# Mosfet_Board.net
KiCad netlist of a schematic drawn in Altium Designer
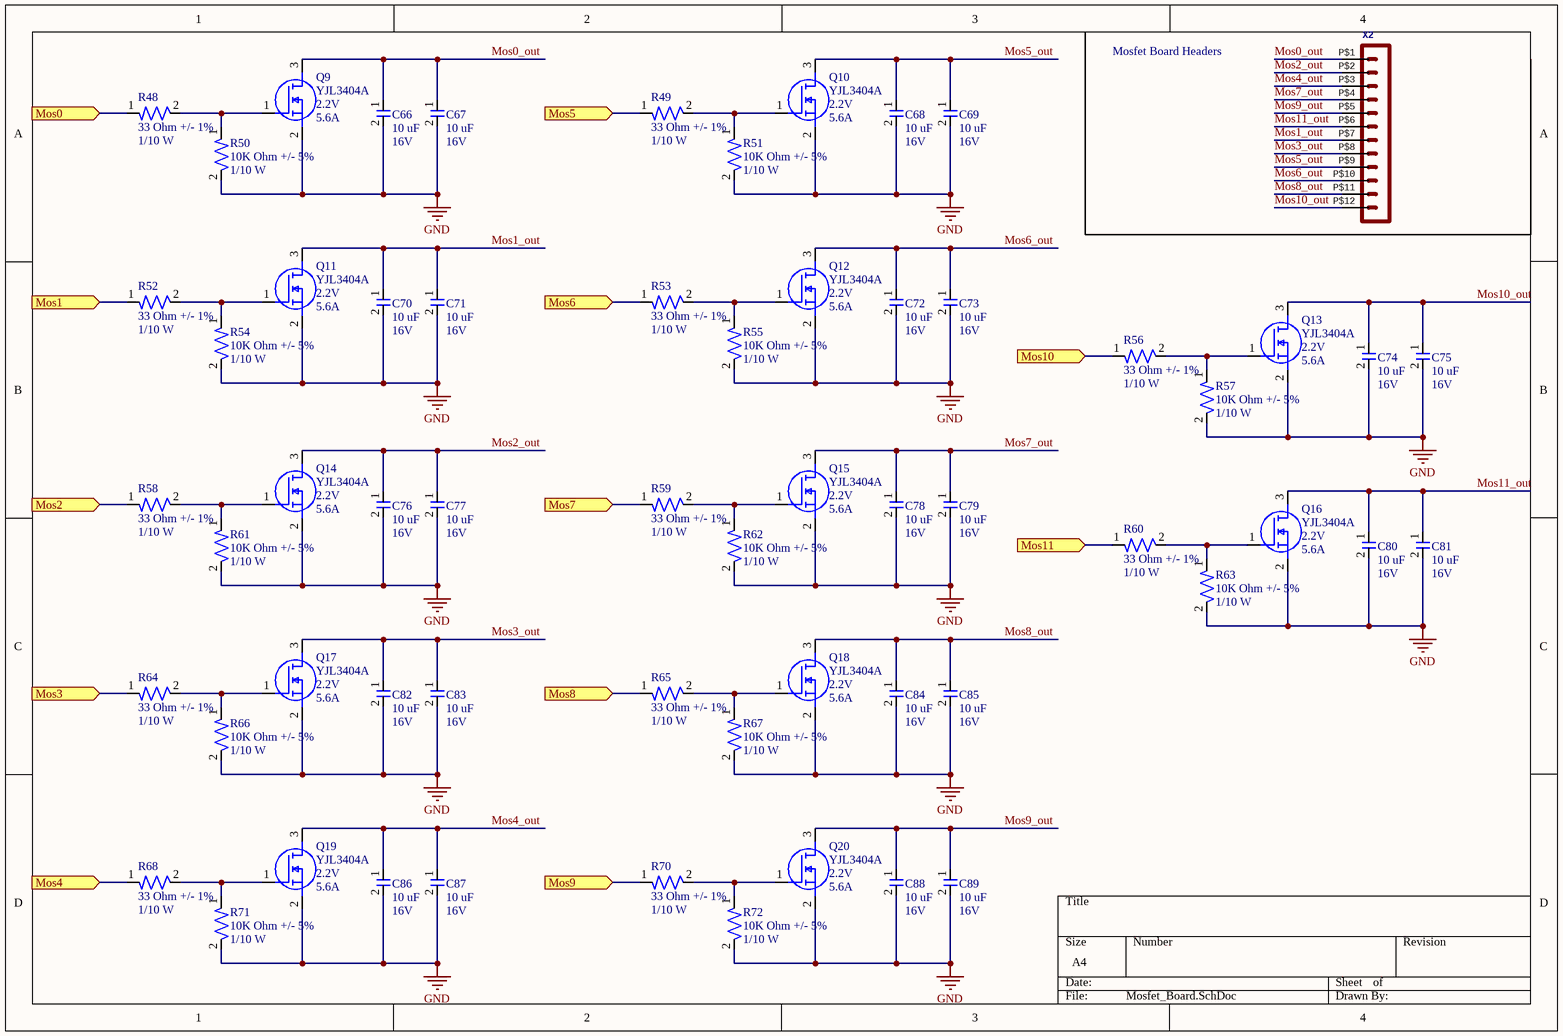
[diagram p0: Mosfet_Board.SchDoc]

(export (version "E")
  (design (tool "Eeschema 10.0.6"))
  (components
    (comp (ref "C66")
      (value "MCS1802GS-20-Z")
      (footprint "CAP-0805")
      (description "10 µF ±10% 16V Ceramic Capacitor X7R 0805 (2012 Metric)")
      (fields (field (name "CAPACITANCE") "10 uF") (field (name "VOLTAGE RATING") "16V"))
      (libsource (lib "MasterLib") (part "CAP-10U-0002"))
    )
    (comp (ref "C67")
      (value "MCS1802GS-20-Z")
      (footprint "CAP-0805")
      (description "10 µF ±10% 16V Ceramic Capacitor X7R 0805 (2012 Metric)")
      (fields (field (name "CAPACITANCE") "10 uF") (field (name "VOLTAGE RATING") "16V"))
      (libsource (lib "MasterLib") (part "CAP-10U-0002"))
    )
    (comp (ref "C68")
      (value "MCS1802GS-20-Z")
      (footprint "CAP-0805")
      (description "10 µF ±10% 16V Ceramic Capacitor X7R 0805 (2012 Metric)")
      (fields (field (name "CAPACITANCE") "10 uF") (field (name "VOLTAGE RATING") "16V"))
      (libsource (lib "MasterLib") (part "CAP-10U-0002"))
    )
    (comp (ref "C69")
      (value "MCS1802GS-20-Z")
      (footprint "CAP-0805")
      (description "10 µF ±10% 16V Ceramic Capacitor X7R 0805 (2012 Metric)")
      (fields (field (name "CAPACITANCE") "10 uF") (field (name "VOLTAGE RATING") "16V"))
      (libsource (lib "MasterLib") (part "CAP-10U-0002"))
    )
    (comp (ref "C70")
      (value "MCS1802GS-20-Z")
      (footprint "CAP-0805")
      (description "10 µF ±10% 16V Ceramic Capacitor X7R 0805 (2012 Metric)")
      (fields (field (name "CAPACITANCE") "10 uF") (field (name "VOLTAGE RATING") "16V"))
      (libsource (lib "MasterLib") (part "CAP-10U-0002"))
    )
    (comp (ref "C71")
      (value "MCS1802GS-20-Z")
      (footprint "CAP-0805")
      (description "10 µF ±10% 16V Ceramic Capacitor X7R 0805 (2012 Metric)")
      (fields (field (name "CAPACITANCE") "10 uF") (field (name "VOLTAGE RATING") "16V"))
      (libsource (lib "MasterLib") (part "CAP-10U-0002"))
    )
    (comp (ref "C72")
      (value "MCS1802GS-20-Z")
      (footprint "CAP-0805")
      (description "10 µF ±10% 16V Ceramic Capacitor X7R 0805 (2012 Metric)")
      (fields (field (name "CAPACITANCE") "10 uF") (field (name "VOLTAGE RATING") "16V"))
      (libsource (lib "MasterLib") (part "CAP-10U-0002"))
    )
    (comp (ref "C73")
      (value "MCS1802GS-20-Z")
      (footprint "CAP-0805")
      (description "10 µF ±10% 16V Ceramic Capacitor X7R 0805 (2012 Metric)")
      (fields (field (name "CAPACITANCE") "10 uF") (field (name "VOLTAGE RATING") "16V"))
      (libsource (lib "MasterLib") (part "CAP-10U-0002"))
    )
    (comp (ref "C74")
      (value "MCS1802GS-20-Z")
      (footprint "CAP-0805")
      (description "10 µF ±10% 16V Ceramic Capacitor X7R 0805 (2012 Metric)")
      (fields (field (name "CAPACITANCE") "10 uF") (field (name "VOLTAGE RATING") "16V"))
      (libsource (lib "MasterLib") (part "CAP-10U-0002"))
    )
    (comp (ref "C75")
      (value "MCS1802GS-20-Z")
      (footprint "CAP-0805")
      (description "10 µF ±10% 16V Ceramic Capacitor X7R 0805 (2012 Metric)")
      (fields (field (name "CAPACITANCE") "10 uF") (field (name "VOLTAGE RATING") "16V"))
      (libsource (lib "MasterLib") (part "CAP-10U-0002"))
    )
    (comp (ref "C76")
      (value "MCS1802GS-20-Z")
      (footprint "CAP-0805")
      (description "10 µF ±10% 16V Ceramic Capacitor X7R 0805 (2012 Metric)")
      (fields (field (name "CAPACITANCE") "10 uF") (field (name "VOLTAGE RATING") "16V"))
      (libsource (lib "MasterLib") (part "CAP-10U-0002"))
    )
    (comp (ref "C77")
      (value "MCS1802GS-20-Z")
      (footprint "CAP-0805")
      (description "10 µF ±10% 16V Ceramic Capacitor X7R 0805 (2012 Metric)")
      (fields (field (name "CAPACITANCE") "10 uF") (field (name "VOLTAGE RATING") "16V"))
      (libsource (lib "MasterLib") (part "CAP-10U-0002"))
    )
    (comp (ref "C78")
      (value "MCS1802GS-20-Z")
      (footprint "CAP-0805")
      (description "10 µF ±10% 16V Ceramic Capacitor X7R 0805 (2012 Metric)")
      (fields (field (name "CAPACITANCE") "10 uF") (field (name "VOLTAGE RATING") "16V"))
      (libsource (lib "MasterLib") (part "CAP-10U-0002"))
    )
    (comp (ref "C79")
      (value "MCS1802GS-20-Z")
      (footprint "CAP-0805")
      (description "10 µF ±10% 16V Ceramic Capacitor X7R 0805 (2012 Metric)")
      (fields (field (name "CAPACITANCE") "10 uF") (field (name "VOLTAGE RATING") "16V"))
      (libsource (lib "MasterLib") (part "CAP-10U-0002"))
    )
    (comp (ref "C80")
      (value "MCS1802GS-20-Z")
      (footprint "CAP-0805")
      (description "10 µF ±10% 16V Ceramic Capacitor X7R 0805 (2012 Metric)")
      (fields (field (name "CAPACITANCE") "10 uF") (field (name "VOLTAGE RATING") "16V"))
      (libsource (lib "MasterLib") (part "CAP-10U-0002"))
    )
    (comp (ref "C81")
      (value "MCS1802GS-20-Z")
      (footprint "CAP-0805")
      (description "10 µF ±10% 16V Ceramic Capacitor X7R 0805 (2012 Metric)")
      (fields (field (name "CAPACITANCE") "10 uF") (field (name "VOLTAGE RATING") "16V"))
      (libsource (lib "MasterLib") (part "CAP-10U-0002"))
    )
    (comp (ref "C82")
      (value "MCS1802GS-20-Z")
      (footprint "CAP-0805")
      (description "10 µF ±10% 16V Ceramic Capacitor X7R 0805 (2012 Metric)")
      (fields (field (name "CAPACITANCE") "10 uF") (field (name "VOLTAGE RATING") "16V"))
      (libsource (lib "MasterLib") (part "CAP-10U-0002"))
    )
    (comp (ref "C83")
      (value "MCS1802GS-20-Z")
      (footprint "CAP-0805")
      (description "10 µF ±10% 16V Ceramic Capacitor X7R 0805 (2012 Metric)")
      (fields (field (name "CAPACITANCE") "10 uF") (field (name "VOLTAGE RATING") "16V"))
      (libsource (lib "MasterLib") (part "CAP-10U-0002"))
    )
    (comp (ref "C84")
      (value "MCS1802GS-20-Z")
      (footprint "CAP-0805")
      (description "10 µF ±10% 16V Ceramic Capacitor X7R 0805 (2012 Metric)")
      (fields (field (name "CAPACITANCE") "10 uF") (field (name "VOLTAGE RATING") "16V"))
      (libsource (lib "MasterLib") (part "CAP-10U-0002"))
    )
    (comp (ref "C85")
      (value "MCS1802GS-20-Z")
      (footprint "CAP-0805")
      (description "10 µF ±10% 16V Ceramic Capacitor X7R 0805 (2012 Metric)")
      (fields (field (name "CAPACITANCE") "10 uF") (field (name "VOLTAGE RATING") "16V"))
      (libsource (lib "MasterLib") (part "CAP-10U-0002"))
    )
    (comp (ref "C86")
      (value "MCS1802GS-20-Z")
      (footprint "CAP-0805")
      (description "10 µF ±10% 16V Ceramic Capacitor X7R 0805 (2012 Metric)")
      (fields (field (name "CAPACITANCE") "10 uF") (field (name "VOLTAGE RATING") "16V"))
      (libsource (lib "MasterLib") (part "CAP-10U-0002"))
    )
    (comp (ref "C87")
      (value "MCS1802GS-20-Z")
      (footprint "CAP-0805")
      (description "10 µF ±10% 16V Ceramic Capacitor X7R 0805 (2012 Metric)")
      (fields (field (name "CAPACITANCE") "10 uF") (field (name "VOLTAGE RATING") "16V"))
      (libsource (lib "MasterLib") (part "CAP-10U-0002"))
    )
    (comp (ref "C88")
      (value "MCS1802GS-20-Z")
      (footprint "CAP-0805")
      (description "10 µF ±10% 16V Ceramic Capacitor X7R 0805 (2012 Metric)")
      (fields (field (name "CAPACITANCE") "10 uF") (field (name "VOLTAGE RATING") "16V"))
      (libsource (lib "MasterLib") (part "CAP-10U-0002"))
    )
    (comp (ref "C89")
      (value "MCS1802GS-20-Z")
      (footprint "CAP-0805")
      (description "10 µF ±10% 16V Ceramic Capacitor X7R 0805 (2012 Metric)")
      (fields (field (name "CAPACITANCE") "10 uF") (field (name "VOLTAGE RATING") "16V"))
      (libsource (lib "MasterLib") (part "CAP-10U-0002"))
    )
    (comp (ref "Q9")
      (value "YJL3404A")
      (footprint "NMOS-SOT23-3")
      (description "N-Channel 30 V 5.6A (Ta) 1.2W (Ta) Surface Mount SOT-23")
      (fields (field (name "VGS(TH)") "2.2V") (field (name "DRAIN CURRENT") "5.6A"))
      (libsource (lib "MasterLib") (part "NMOS-5.6A-0001"))
    )
    (comp (ref "Q10")
      (value "YJL3404A")
      (footprint "NMOS-SOT23-3")
      (description "N-Channel 30 V 5.6A (Ta) 1.2W (Ta) Surface Mount SOT-23")
      (fields (field (name "VGS(TH)") "2.2V") (field (name "DRAIN CURRENT") "5.6A"))
      (libsource (lib "MasterLib") (part "NMOS-5.6A-0001"))
    )
    (comp (ref "Q11")
      (value "YJL3404A")
      (footprint "NMOS-SOT23-3")
      (description "N-Channel 30 V 5.6A (Ta) 1.2W (Ta) Surface Mount SOT-23")
      (fields (field (name "VGS(TH)") "2.2V") (field (name "DRAIN CURRENT") "5.6A"))
      (libsource (lib "MasterLib") (part "NMOS-5.6A-0001"))
    )
    (comp (ref "Q12")
      (value "YJL3404A")
      (footprint "NMOS-SOT23-3")
      (description "N-Channel 30 V 5.6A (Ta) 1.2W (Ta) Surface Mount SOT-23")
      (fields (field (name "VGS(TH)") "2.2V") (field (name "DRAIN CURRENT") "5.6A"))
      (libsource (lib "MasterLib") (part "NMOS-5.6A-0001"))
    )
    (comp (ref "Q13")
      (value "YJL3404A")
      (footprint "NMOS-SOT23-3")
      (description "N-Channel 30 V 5.6A (Ta) 1.2W (Ta) Surface Mount SOT-23")
      (fields (field (name "VGS(TH)") "2.2V") (field (name "DRAIN CURRENT") "5.6A"))
      (libsource (lib "MasterLib") (part "NMOS-5.6A-0001"))
    )
    (comp (ref "Q14")
      (value "YJL3404A")
      (footprint "NMOS-SOT23-3")
      (description "N-Channel 30 V 5.6A (Ta) 1.2W (Ta) Surface Mount SOT-23")
      (fields (field (name "VGS(TH)") "2.2V") (field (name "DRAIN CURRENT") "5.6A"))
      (libsource (lib "MasterLib") (part "NMOS-5.6A-0001"))
    )
    (comp (ref "Q15")
      (value "YJL3404A")
      (footprint "NMOS-SOT23-3")
      (description "N-Channel 30 V 5.6A (Ta) 1.2W (Ta) Surface Mount SOT-23")
      (fields (field (name "VGS(TH)") "2.2V") (field (name "DRAIN CURRENT") "5.6A"))
      (libsource (lib "MasterLib") (part "NMOS-5.6A-0001"))
    )
    (comp (ref "Q16")
      (value "YJL3404A")
      (footprint "NMOS-SOT23-3")
      (description "N-Channel 30 V 5.6A (Ta) 1.2W (Ta) Surface Mount SOT-23")
      (fields (field (name "VGS(TH)") "2.2V") (field (name "DRAIN CURRENT") "5.6A"))
      (libsource (lib "MasterLib") (part "NMOS-5.6A-0001"))
    )
    (comp (ref "Q17")
      (value "YJL3404A")
      (footprint "NMOS-SOT23-3")
      (description "N-Channel 30 V 5.6A (Ta) 1.2W (Ta) Surface Mount SOT-23")
      (fields (field (name "VGS(TH)") "2.2V") (field (name "DRAIN CURRENT") "5.6A"))
      (libsource (lib "MasterLib") (part "NMOS-5.6A-0001"))
    )
    (comp (ref "Q18")
      (value "YJL3404A")
      (footprint "NMOS-SOT23-3")
      (description "N-Channel 30 V 5.6A (Ta) 1.2W (Ta) Surface Mount SOT-23")
      (fields (field (name "VGS(TH)") "2.2V") (field (name "DRAIN CURRENT") "5.6A"))
      (libsource (lib "MasterLib") (part "NMOS-5.6A-0001"))
    )
    (comp (ref "Q19")
      (value "YJL3404A")
      (footprint "NMOS-SOT23-3")
      (description "N-Channel 30 V 5.6A (Ta) 1.2W (Ta) Surface Mount SOT-23")
      (fields (field (name "VGS(TH)") "2.2V") (field (name "DRAIN CURRENT") "5.6A"))
      (libsource (lib "MasterLib") (part "NMOS-5.6A-0001"))
    )
    (comp (ref "Q20")
      (value "YJL3404A")
      (footprint "NMOS-SOT23-3")
      (description "N-Channel 30 V 5.6A (Ta) 1.2W (Ta) Surface Mount SOT-23")
      (fields (field (name "VGS(TH)") "2.2V") (field (name "DRAIN CURRENT") "5.6A"))
      (libsource (lib "MasterLib") (part "NMOS-5.6A-0001"))
    )
    (comp (ref "R48")
      (value "ERJ2RKF33R0X")
      (footprint "RES-0402")
      (description "100mW Thick Film Resistors ±100ppm/℃ ±1% -55℃~+155℃ 33Ω 0402  Chip Resistor - Surface Mount ROHS")
      (fields
        (field (name "RESISTANCE") "33 Ohm +/- 1%")
        (field (name "POWER") "1/10 W")
        (field (name "JLC PART NUMBER") "C278594")
      )
      (libsource (lib "MasterLib") (part "RES-33-0003-JLC"))
    )
    (comp (ref "R49")
      (value "ERJ2RKF33R0X")
      (footprint "RES-0402")
      (description "100mW Thick Film Resistors ±100ppm/℃ ±1% -55℃~+155℃ 33Ω 0402  Chip Resistor - Surface Mount ROHS")
      (fields
        (field (name "RESISTANCE") "33 Ohm +/- 1%")
        (field (name "POWER") "1/10 W")
        (field (name "JLC PART NUMBER") "C278594")
      )
      (libsource (lib "MasterLib") (part "RES-33-0003-JLC"))
    )
    (comp (ref "R50")
      (value "ERJ2GEJ103X")
      (footprint "RES-0402")
      (fields
        (field (name "RESISTANCE") "10K Ohm +/- 5%")
        (field (name "POWER") "1/10 W")
        (field (name "JLC PART NUMBER") "C278577")
      )
      (libsource (lib "MasterLib") (part "RES-10K-0003-JLC"))
    )
    (comp (ref "R51")
      (value "ERJ2GEJ103X")
      (footprint "RES-0402")
      (fields
        (field (name "RESISTANCE") "10K Ohm +/- 5%")
        (field (name "POWER") "1/10 W")
        (field (name "JLC PART NUMBER") "C278577")
      )
      (libsource (lib "MasterLib") (part "RES-10K-0003-JLC"))
    )
    (comp (ref "R52")
      (value "ERJ2RKF33R0X")
      (footprint "RES-0402")
      (description "100mW Thick Film Resistors ±100ppm/℃ ±1% -55℃~+155℃ 33Ω 0402  Chip Resistor - Surface Mount ROHS")
      (fields
        (field (name "RESISTANCE") "33 Ohm +/- 1%")
        (field (name "POWER") "1/10 W")
        (field (name "JLC PART NUMBER") "C278594")
      )
      (libsource (lib "MasterLib") (part "RES-33-0003-JLC"))
    )
    (comp (ref "R53")
      (value "ERJ2RKF33R0X")
      (footprint "RES-0402")
      (description "100mW Thick Film Resistors ±100ppm/℃ ±1% -55℃~+155℃ 33Ω 0402  Chip Resistor - Surface Mount ROHS")
      (fields
        (field (name "RESISTANCE") "33 Ohm +/- 1%")
        (field (name "POWER") "1/10 W")
        (field (name "JLC PART NUMBER") "C278594")
      )
      (libsource (lib "MasterLib") (part "RES-33-0003-JLC"))
    )
    (comp (ref "R54")
      (value "ERJ2GEJ103X")
      (footprint "RES-0402")
      (fields
        (field (name "RESISTANCE") "10K Ohm +/- 5%")
        (field (name "POWER") "1/10 W")
        (field (name "JLC PART NUMBER") "C278577")
      )
      (libsource (lib "MasterLib") (part "RES-10K-0003-JLC"))
    )
    (comp (ref "R55")
      (value "ERJ2GEJ103X")
      (footprint "RES-0402")
      (fields
        (field (name "RESISTANCE") "10K Ohm +/- 5%")
        (field (name "POWER") "1/10 W")
        (field (name "JLC PART NUMBER") "C278577")
      )
      (libsource (lib "MasterLib") (part "RES-10K-0003-JLC"))
    )
    (comp (ref "R56")
      (value "ERJ2RKF33R0X")
      (footprint "RES-0402")
      (description "100mW Thick Film Resistors ±100ppm/℃ ±1% -55℃~+155℃ 33Ω 0402  Chip Resistor - Surface Mount ROHS")
      (fields
        (field (name "RESISTANCE") "33 Ohm +/- 1%")
        (field (name "POWER") "1/10 W")
        (field (name "JLC PART NUMBER") "C278594")
      )
      (libsource (lib "MasterLib") (part "RES-33-0003-JLC"))
    )
    (comp (ref "R57")
      (value "ERJ2GEJ103X")
      (footprint "RES-0402")
      (fields
        (field (name "RESISTANCE") "10K Ohm +/- 5%")
        (field (name "POWER") "1/10 W")
        (field (name "JLC PART NUMBER") "C278577")
      )
      (libsource (lib "MasterLib") (part "RES-10K-0003-JLC"))
    )
    (comp (ref "R58")
      (value "ERJ2RKF33R0X")
      (footprint "RES-0402")
      (description "100mW Thick Film Resistors ±100ppm/℃ ±1% -55℃~+155℃ 33Ω 0402  Chip Resistor - Surface Mount ROHS")
      (fields
        (field (name "RESISTANCE") "33 Ohm +/- 1%")
        (field (name "POWER") "1/10 W")
        (field (name "JLC PART NUMBER") "C278594")
      )
      (libsource (lib "MasterLib") (part "RES-33-0003-JLC"))
    )
    (comp (ref "R59")
      (value "ERJ2RKF33R0X")
      (footprint "RES-0402")
      (description "100mW Thick Film Resistors ±100ppm/℃ ±1% -55℃~+155℃ 33Ω 0402  Chip Resistor - Surface Mount ROHS")
      (fields
        (field (name "RESISTANCE") "33 Ohm +/- 1%")
        (field (name "POWER") "1/10 W")
        (field (name "JLC PART NUMBER") "C278594")
      )
      (libsource (lib "MasterLib") (part "RES-33-0003-JLC"))
    )
    (comp (ref "R60")
      (value "ERJ2RKF33R0X")
      (footprint "RES-0402")
      (description "100mW Thick Film Resistors ±100ppm/℃ ±1% -55℃~+155℃ 33Ω 0402  Chip Resistor - Surface Mount ROHS")
      (fields
        (field (name "RESISTANCE") "33 Ohm +/- 1%")
        (field (name "POWER") "1/10 W")
        (field (name "JLC PART NUMBER") "C278594")
      )
      (libsource (lib "MasterLib") (part "RES-33-0003-JLC"))
    )
    (comp (ref "R61")
      (value "ERJ2GEJ103X")
      (footprint "RES-0402")
      (fields
        (field (name "RESISTANCE") "10K Ohm +/- 5%")
        (field (name "POWER") "1/10 W")
        (field (name "JLC PART NUMBER") "C278577")
      )
      (libsource (lib "MasterLib") (part "RES-10K-0003-JLC"))
    )
    (comp (ref "R62")
      (value "ERJ2GEJ103X")
      (footprint "RES-0402")
      (fields
        (field (name "RESISTANCE") "10K Ohm +/- 5%")
        (field (name "POWER") "1/10 W")
        (field (name "JLC PART NUMBER") "C278577")
      )
      (libsource (lib "MasterLib") (part "RES-10K-0003-JLC"))
    )
    (comp (ref "R63")
      (value "ERJ2GEJ103X")
      (footprint "RES-0402")
      (fields
        (field (name "RESISTANCE") "10K Ohm +/- 5%")
        (field (name "POWER") "1/10 W")
        (field (name "JLC PART NUMBER") "C278577")
      )
      (libsource (lib "MasterLib") (part "RES-10K-0003-JLC"))
    )
    (comp (ref "R64")
      (value "ERJ2RKF33R0X")
      (footprint "RES-0402")
      (description "100mW Thick Film Resistors ±100ppm/℃ ±1% -55℃~+155℃ 33Ω 0402  Chip Resistor - Surface Mount ROHS")
      (fields
        (field (name "RESISTANCE") "33 Ohm +/- 1%")
        (field (name "POWER") "1/10 W")
        (field (name "JLC PART NUMBER") "C278594")
      )
      (libsource (lib "MasterLib") (part "RES-33-0003-JLC"))
    )
    (comp (ref "R65")
      (value "ERJ2RKF33R0X")
      (footprint "RES-0402")
      (description "100mW Thick Film Resistors ±100ppm/℃ ±1% -55℃~+155℃ 33Ω 0402  Chip Resistor - Surface Mount ROHS")
      (fields
        (field (name "RESISTANCE") "33 Ohm +/- 1%")
        (field (name "POWER") "1/10 W")
        (field (name "JLC PART NUMBER") "C278594")
      )
      (libsource (lib "MasterLib") (part "RES-33-0003-JLC"))
    )
    (comp (ref "R66")
      (value "ERJ2GEJ103X")
      (footprint "RES-0402")
      (fields
        (field (name "RESISTANCE") "10K Ohm +/- 5%")
        (field (name "POWER") "1/10 W")
        (field (name "JLC PART NUMBER") "C278577")
      )
      (libsource (lib "MasterLib") (part "RES-10K-0003-JLC"))
    )
    (comp (ref "R67")
      (value "ERJ2GEJ103X")
      (footprint "RES-0402")
      (fields
        (field (name "RESISTANCE") "10K Ohm +/- 5%")
        (field (name "POWER") "1/10 W")
        (field (name "JLC PART NUMBER") "C278577")
      )
      (libsource (lib "MasterLib") (part "RES-10K-0003-JLC"))
    )
    (comp (ref "R68")
      (value "ERJ2RKF33R0X")
      (footprint "RES-0402")
      (description "100mW Thick Film Resistors ±100ppm/℃ ±1% -55℃~+155℃ 33Ω 0402  Chip Resistor - Surface Mount ROHS")
      (fields
        (field (name "RESISTANCE") "33 Ohm +/- 1%")
        (field (name "POWER") "1/10 W")
        (field (name "JLC PART NUMBER") "C278594")
      )
      (libsource (lib "MasterLib") (part "RES-33-0003-JLC"))
    )
    (comp (ref "R70")
      (value "ERJ2RKF33R0X")
      (footprint "RES-0402")
      (description "100mW Thick Film Resistors ±100ppm/℃ ±1% -55℃~+155℃ 33Ω 0402  Chip Resistor - Surface Mount ROHS")
      (fields
        (field (name "RESISTANCE") "33 Ohm +/- 1%")
        (field (name "POWER") "1/10 W")
        (field (name "JLC PART NUMBER") "C278594")
      )
      (libsource (lib "MasterLib") (part "RES-33-0003-JLC"))
    )
    (comp (ref "R71")
      (value "ERJ2GEJ103X")
      (footprint "RES-0402")
      (fields
        (field (name "RESISTANCE") "10K Ohm +/- 5%")
        (field (name "POWER") "1/10 W")
        (field (name "JLC PART NUMBER") "C278577")
      )
      (libsource (lib "MasterLib") (part "RES-10K-0003-JLC"))
    )
    (comp (ref "R72")
      (value "ERJ2GEJ103X")
      (footprint "RES-0402")
      (fields
        (field (name "RESISTANCE") "10K Ohm +/- 5%")
        (field (name "POWER") "1/10 W")
        (field (name "JLC PART NUMBER") "C278577")
      )
      (libsource (lib "MasterLib") (part "RES-10K-0003-JLC"))
    )
    (comp (ref "X2")
      (value "Molex - Micro-Fit 3.0 Series connector,  3.00mm (0.118\") pitch header, 12 positions.")
      (footprint "44764-1201")
      (libsource (lib "Molex Microfit") (part "HEADER_POS12_?44764-1201"))
    )
  )
  (nets
    (net (code "1") (name "/Mos0") (class "Default")
      (node (ref "R48") (pin "1") (pinfunction "1_1") (pintype "passive"))
    )
    (net (code "2") (name "/Mos0_out") (class "Default")
      (node (ref "C66") (pin "1") (pinfunction "1_1") (pintype "passive"))
      (node (ref "C67") (pin "1") (pinfunction "1_1") (pintype "passive"))
      (node (ref "Q9") (pin "3") (pinfunction "D_3") (pintype "passive"))
      (node (ref "X2") (pin "P$1") (pinfunction "1_P$1") (pintype "passive"))
    )
    (net (code "3") (name "/Mos1") (class "Default")
      (node (ref "R52") (pin "1") (pinfunction "1_1") (pintype "passive"))
    )
    (net (code "4") (name "/Mos1_out") (class "Default")
      (node (ref "C70") (pin "1") (pinfunction "1_1") (pintype "passive"))
      (node (ref "C71") (pin "1") (pinfunction "1_1") (pintype "passive"))
      (node (ref "Q11") (pin "3") (pinfunction "D_3") (pintype "passive"))
      (node (ref "X2") (pin "P$7") (pinfunction "7_P$7") (pintype "passive"))
    )
    (net (code "5") (name "/Mos2") (class "Default")
      (node (ref "R58") (pin "1") (pinfunction "1_1") (pintype "passive"))
    )
    (net (code "6") (name "/Mos2_out") (class "Default")
      (node (ref "C76") (pin "1") (pinfunction "1_1") (pintype "passive"))
      (node (ref "C77") (pin "1") (pinfunction "1_1") (pintype "passive"))
      (node (ref "Q14") (pin "3") (pinfunction "D_3") (pintype "passive"))
      (node (ref "X2") (pin "P$2") (pinfunction "2_P$2") (pintype "passive"))
    )
    (net (code "7") (name "/Mos3") (class "Default")
      (node (ref "R64") (pin "1") (pinfunction "1_1") (pintype "passive"))
    )
    (net (code "8") (name "/Mos3_out") (class "Default")
      (node (ref "C82") (pin "1") (pinfunction "1_1") (pintype "passive"))
      (node (ref "C83") (pin "1") (pinfunction "1_1") (pintype "passive"))
      (node (ref "Q17") (pin "3") (pinfunction "D_3") (pintype "passive"))
      (node (ref "X2") (pin "P$8") (pinfunction "8_P$8") (pintype "passive"))
    )
    (net (code "9") (name "/Mos4") (class "Default")
      (node (ref "R68") (pin "1") (pinfunction "1_1") (pintype "passive"))
    )
    (net (code "10") (name "/Mos4_out") (class "Default")
      (node (ref "C86") (pin "1") (pinfunction "1_1") (pintype "passive"))
      (node (ref "C87") (pin "1") (pinfunction "1_1") (pintype "passive"))
      (node (ref "Q19") (pin "3") (pinfunction "D_3") (pintype "passive"))
      (node (ref "X2") (pin "P$3") (pinfunction "3_P$3") (pintype "passive"))
    )
    (net (code "11") (name "/Mos5") (class "Default")
      (node (ref "R49") (pin "1") (pinfunction "1_1") (pintype "passive"))
    )
    (net (code "12") (name "/Mos5_out") (class "Default")
      (node (ref "C68") (pin "1") (pinfunction "1_1") (pintype "passive"))
      (node (ref "C69") (pin "1") (pinfunction "1_1") (pintype "passive"))
      (node (ref "Q10") (pin "3") (pinfunction "D_3") (pintype "passive"))
      (node (ref "X2") (pin "P$9") (pinfunction "9_P$9") (pintype "passive"))
    )
    (net (code "13") (name "/Mos6") (class "Default")
      (node (ref "R53") (pin "1") (pinfunction "1_1") (pintype "passive"))
    )
    (net (code "14") (name "/Mos6_out") (class "Default")
      (node (ref "C72") (pin "1") (pinfunction "1_1") (pintype "passive"))
      (node (ref "C73") (pin "1") (pinfunction "1_1") (pintype "passive"))
      (node (ref "Q12") (pin "3") (pinfunction "D_3") (pintype "passive"))
      (node (ref "X2") (pin "P$10") (pinfunction "10_P$10") (pintype "passive"))
    )
    (net (code "15") (name "/Mos7") (class "Default")
      (node (ref "R59") (pin "1") (pinfunction "1_1") (pintype "passive"))
    )
    (net (code "16") (name "/Mos7_out") (class "Default")
      (node (ref "C78") (pin "1") (pinfunction "1_1") (pintype "passive"))
      (node (ref "C79") (pin "1") (pinfunction "1_1") (pintype "passive"))
      (node (ref "Q15") (pin "3") (pinfunction "D_3") (pintype "passive"))
      (node (ref "X2") (pin "P$4") (pinfunction "4_P$4") (pintype "passive"))
    )
    (net (code "17") (name "/Mos8") (class "Default")
      (node (ref "R65") (pin "1") (pinfunction "1_1") (pintype "passive"))
    )
    (net (code "18") (name "/Mos8_out") (class "Default")
      (node (ref "C84") (pin "1") (pinfunction "1_1") (pintype "passive"))
      (node (ref "C85") (pin "1") (pinfunction "1_1") (pintype "passive"))
      (node (ref "Q18") (pin "3") (pinfunction "D_3") (pintype "passive"))
      (node (ref "X2") (pin "P$11") (pinfunction "11_P$11") (pintype "passive"))
    )
    (net (code "19") (name "/Mos9") (class "Default")
      (node (ref "R70") (pin "1") (pinfunction "1_1") (pintype "passive"))
    )
    (net (code "20") (name "/Mos9_out") (class "Default")
      (node (ref "C88") (pin "1") (pinfunction "1_1") (pintype "passive"))
      (node (ref "C89") (pin "1") (pinfunction "1_1") (pintype "passive"))
      (node (ref "Q20") (pin "3") (pinfunction "D_3") (pintype "passive"))
      (node (ref "X2") (pin "P$5") (pinfunction "5_P$5") (pintype "passive"))
    )
    (net (code "21") (name "/Mos10") (class "Default")
      (node (ref "R56") (pin "1") (pinfunction "1_1") (pintype "passive"))
    )
    (net (code "22") (name "/Mos10_out") (class "Default")
      (node (ref "C74") (pin "1") (pinfunction "1_1") (pintype "passive"))
      (node (ref "C75") (pin "1") (pinfunction "1_1") (pintype "passive"))
      (node (ref "Q13") (pin "3") (pinfunction "D_3") (pintype "passive"))
      (node (ref "X2") (pin "P$12") (pinfunction "12_P$12") (pintype "passive"))
    )
    (net (code "23") (name "/Mos11") (class "Default")
      (node (ref "R60") (pin "1") (pinfunction "1_1") (pintype "passive"))
    )
    (net (code "24") (name "/Mos11_out") (class "Default")
      (node (ref "C80") (pin "1") (pinfunction "1_1") (pintype "passive"))
      (node (ref "C81") (pin "1") (pinfunction "1_1") (pintype "passive"))
      (node (ref "Q16") (pin "3") (pinfunction "D_3") (pintype "passive"))
      (node (ref "X2") (pin "P$6") (pinfunction "6_P$6") (pintype "passive"))
    )
    (net (code "25") (name "GND") (class "Default")
      (node (ref "C66") (pin "2") (pinfunction "2_2") (pintype "passive"))
      (node (ref "C67") (pin "2") (pinfunction "2_2") (pintype "passive"))
      (node (ref "C68") (pin "2") (pinfunction "2_2") (pintype "passive"))
      (node (ref "C69") (pin "2") (pinfunction "2_2") (pintype "passive"))
      (node (ref "C70") (pin "2") (pinfunction "2_2") (pintype "passive"))
      (node (ref "C71") (pin "2") (pinfunction "2_2") (pintype "passive"))
      (node (ref "C72") (pin "2") (pinfunction "2_2") (pintype "passive"))
      (node (ref "C73") (pin "2") (pinfunction "2_2") (pintype "passive"))
      (node (ref "C74") (pin "2") (pinfunction "2_2") (pintype "passive"))
      (node (ref "C75") (pin "2") (pinfunction "2_2") (pintype "passive"))
      (node (ref "C76") (pin "2") (pinfunction "2_2") (pintype "passive"))
      (node (ref "C77") (pin "2") (pinfunction "2_2") (pintype "passive"))
      (node (ref "C78") (pin "2") (pinfunction "2_2") (pintype "passive"))
      (node (ref "C79") (pin "2") (pinfunction "2_2") (pintype "passive"))
      (node (ref "C80") (pin "2") (pinfunction "2_2") (pintype "passive"))
      (node (ref "C81") (pin "2") (pinfunction "2_2") (pintype "passive"))
      (node (ref "C82") (pin "2") (pinfunction "2_2") (pintype "passive"))
      (node (ref "C83") (pin "2") (pinfunction "2_2") (pintype "passive"))
      (node (ref "C84") (pin "2") (pinfunction "2_2") (pintype "passive"))
      (node (ref "C85") (pin "2") (pinfunction "2_2") (pintype "passive"))
      (node (ref "C86") (pin "2") (pinfunction "2_2") (pintype "passive"))
      (node (ref "C87") (pin "2") (pinfunction "2_2") (pintype "passive"))
      (node (ref "C88") (pin "2") (pinfunction "2_2") (pintype "passive"))
      (node (ref "C89") (pin "2") (pinfunction "2_2") (pintype "passive"))
      (node (ref "Q10") (pin "2") (pinfunction "S_2") (pintype "passive"))
      (node (ref "Q11") (pin "2") (pinfunction "S_2") (pintype "passive"))
      (node (ref "Q12") (pin "2") (pinfunction "S_2") (pintype "passive"))
      (node (ref "Q13") (pin "2") (pinfunction "S_2") (pintype "passive"))
      (node (ref "Q14") (pin "2") (pinfunction "S_2") (pintype "passive"))
      (node (ref "Q15") (pin "2") (pinfunction "S_2") (pintype "passive"))
      (node (ref "Q16") (pin "2") (pinfunction "S_2") (pintype "passive"))
      (node (ref "Q17") (pin "2") (pinfunction "S_2") (pintype "passive"))
      (node (ref "Q18") (pin "2") (pinfunction "S_2") (pintype "passive"))
      (node (ref "Q19") (pin "2") (pinfunction "S_2") (pintype "passive"))
      (node (ref "Q20") (pin "2") (pinfunction "S_2") (pintype "passive"))
      (node (ref "Q9") (pin "2") (pinfunction "S_2") (pintype "passive"))
      (node (ref "R50") (pin "2") (pinfunction "2_2") (pintype "passive"))
      (node (ref "R51") (pin "2") (pinfunction "2_2") (pintype "passive"))
      (node (ref "R54") (pin "2") (pinfunction "2_2") (pintype "passive"))
      (node (ref "R55") (pin "2") (pinfunction "2_2") (pintype "passive"))
      (node (ref "R57") (pin "2") (pinfunction "2_2") (pintype "passive"))
      (node (ref "R61") (pin "2") (pinfunction "2_2") (pintype "passive"))
      (node (ref "R62") (pin "2") (pinfunction "2_2") (pintype "passive"))
      (node (ref "R63") (pin "2") (pinfunction "2_2") (pintype "passive"))
      (node (ref "R66") (pin "2") (pinfunction "2_2") (pintype "passive"))
      (node (ref "R67") (pin "2") (pinfunction "2_2") (pintype "passive"))
      (node (ref "R71") (pin "2") (pinfunction "2_2") (pintype "passive"))
      (node (ref "R72") (pin "2") (pinfunction "2_2") (pintype "passive"))
    )
    (net (code "26") (name "Net-(Q9-G)") (class "Default")
      (node (ref "Q9") (pin "1") (pinfunction "G_1") (pintype "passive"))
      (node (ref "R48") (pin "2") (pinfunction "2_2") (pintype "passive"))
      (node (ref "R50") (pin "1") (pinfunction "1_1") (pintype "passive"))
    )
    (net (code "27") (name "Net-(Q10-G)") (class "Default")
      (node (ref "Q10") (pin "1") (pinfunction "G_1") (pintype "passive"))
      (node (ref "R49") (pin "2") (pinfunction "2_2") (pintype "passive"))
      (node (ref "R51") (pin "1") (pinfunction "1_1") (pintype "passive"))
    )
    (net (code "28") (name "Net-(Q11-G)") (class "Default")
      (node (ref "Q11") (pin "1") (pinfunction "G_1") (pintype "passive"))
      (node (ref "R52") (pin "2") (pinfunction "2_2") (pintype "passive"))
      (node (ref "R54") (pin "1") (pinfunction "1_1") (pintype "passive"))
    )
    (net (code "29") (name "Net-(Q12-G)") (class "Default")
      (node (ref "Q12") (pin "1") (pinfunction "G_1") (pintype "passive"))
      (node (ref "R53") (pin "2") (pinfunction "2_2") (pintype "passive"))
      (node (ref "R55") (pin "1") (pinfunction "1_1") (pintype "passive"))
    )
    (net (code "30") (name "Net-(Q13-G)") (class "Default")
      (node (ref "Q13") (pin "1") (pinfunction "G_1") (pintype "passive"))
      (node (ref "R56") (pin "2") (pinfunction "2_2") (pintype "passive"))
      (node (ref "R57") (pin "1") (pinfunction "1_1") (pintype "passive"))
    )
    (net (code "31") (name "Net-(Q14-G)") (class "Default")
      (node (ref "Q14") (pin "1") (pinfunction "G_1") (pintype "passive"))
      (node (ref "R58") (pin "2") (pinfunction "2_2") (pintype "passive"))
      (node (ref "R61") (pin "1") (pinfunction "1_1") (pintype "passive"))
    )
    (net (code "32") (name "Net-(Q15-G)") (class "Default")
      (node (ref "Q15") (pin "1") (pinfunction "G_1") (pintype "passive"))
      (node (ref "R59") (pin "2") (pinfunction "2_2") (pintype "passive"))
      (node (ref "R62") (pin "1") (pinfunction "1_1") (pintype "passive"))
    )
    (net (code "33") (name "Net-(Q16-G)") (class "Default")
      (node (ref "Q16") (pin "1") (pinfunction "G_1") (pintype "passive"))
      (node (ref "R60") (pin "2") (pinfunction "2_2") (pintype "passive"))
      (node (ref "R63") (pin "1") (pinfunction "1_1") (pintype "passive"))
    )
    (net (code "34") (name "Net-(Q17-G)") (class "Default")
      (node (ref "Q17") (pin "1") (pinfunction "G_1") (pintype "passive"))
      (node (ref "R64") (pin "2") (pinfunction "2_2") (pintype "passive"))
      (node (ref "R66") (pin "1") (pinfunction "1_1") (pintype "passive"))
    )
    (net (code "35") (name "Net-(Q18-G)") (class "Default")
      (node (ref "Q18") (pin "1") (pinfunction "G_1") (pintype "passive"))
      (node (ref "R65") (pin "2") (pinfunction "2_2") (pintype "passive"))
      (node (ref "R67") (pin "1") (pinfunction "1_1") (pintype "passive"))
    )
    (net (code "36") (name "Net-(Q19-G)") (class "Default")
      (node (ref "Q19") (pin "1") (pinfunction "G_1") (pintype "passive"))
      (node (ref "R68") (pin "2") (pinfunction "2_2") (pintype "passive"))
      (node (ref "R71") (pin "1") (pinfunction "1_1") (pintype "passive"))
    )
    (net (code "37") (name "Net-(Q20-G)") (class "Default")
      (node (ref "Q20") (pin "1") (pinfunction "G_1") (pintype "passive"))
      (node (ref "R70") (pin "2") (pinfunction "2_2") (pintype "passive"))
      (node (ref "R72") (pin "1") (pinfunction "1_1") (pintype "passive"))
    )
  )
)
